# HSDL-9100.net
KiCad netlist of a schematic drawn in EAGLE
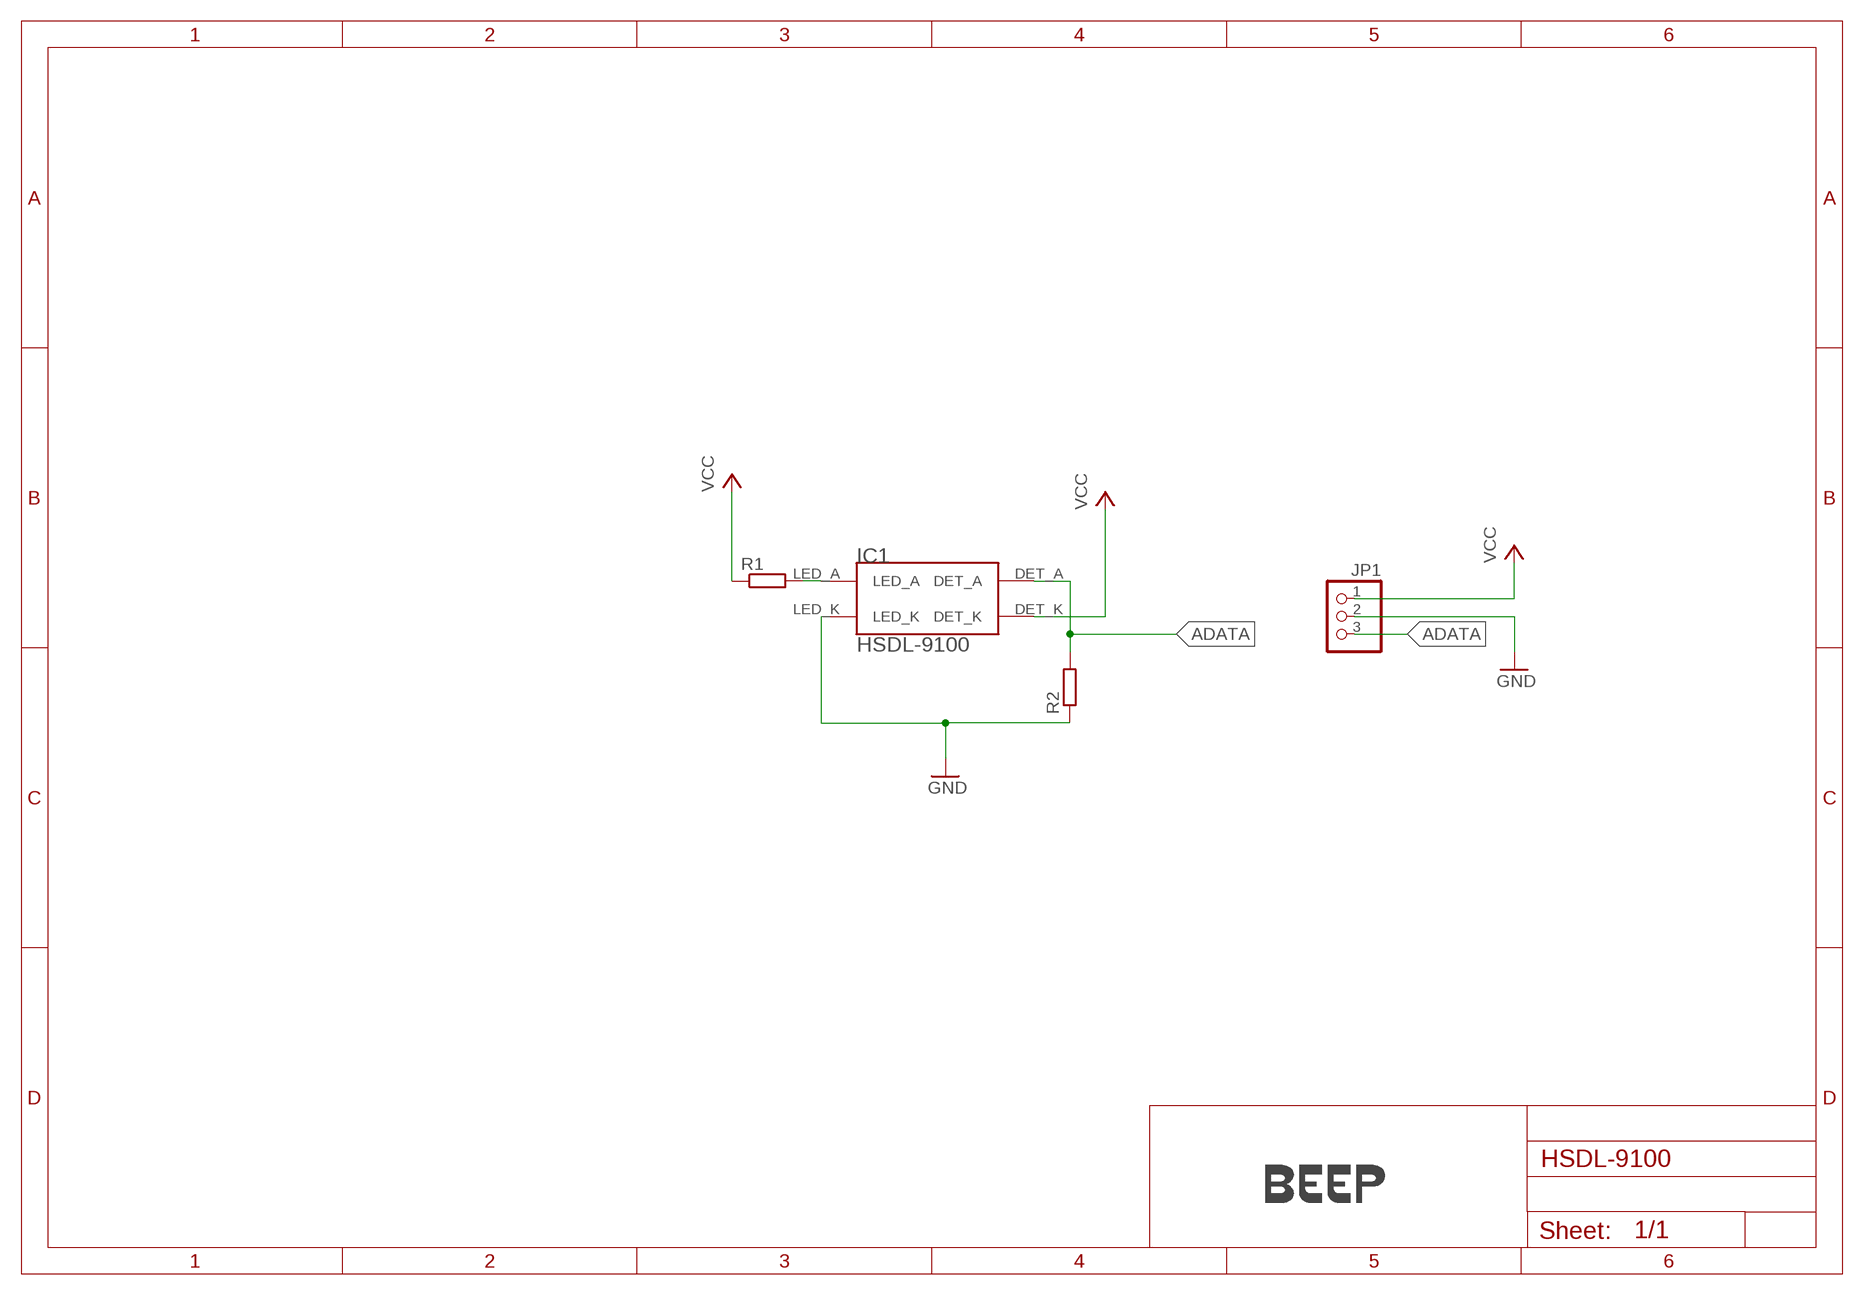
[diagram p0: schematic, sheet 1]

(export (version "E")
  (design (tool "Eeschema 10.0.6"))
  (components
    (comp (ref "IC1")
      (value "HSDL-9100")
      (footprint "eagle-import:HSDL-9100")
      (libsource (lib "eagle-import") (part "HSDL-9100"))
    )
    (comp (ref "JP1")
      (value "PINHD-1X3")
      (footprint "eagle-import:1X03")
      (libsource (lib "eagle-import") (part "PINHD-1X3"))
    )
    (comp (ref "R1")
      (value "R-EU_M0805")
      (footprint "eagle-import:M0805")
      (libsource (lib "eagle-import") (part "R-EU_M0805"))
    )
    (comp (ref "R2")
      (value "R-EU_M0805")
      (footprint "eagle-import:M0805")
      (libsource (lib "eagle-import") (part "R-EU_M0805"))
    )
    (comp (ref "U$1")
      (value "LOGO-COPPER3")
      (footprint "eagle-import:COPPER3")
      (libsource (lib "eagle-import") (part "LOGO-COPPER3"))
    )
  )
  (nets
    (net (code "1") (name "ADATA") (class "Default")
      (node (ref "IC1") (pin "DET_A") (pinfunction "DET_A_DET_A") (pintype "bidirectional"))
      (node (ref "JP1") (pin "3") (pinfunction "3_3") (pintype "passive"))
      (node (ref "R2") (pin "2") (pinfunction "2_2") (pintype "passive"))
    )
    (net (code "2") (name "GND") (class "Default")
      (node (ref "IC1") (pin "LED_K") (pinfunction "LED_K_LED_K") (pintype "bidirectional"))
      (node (ref "JP1") (pin "2") (pinfunction "2_2") (pintype "passive"))
      (node (ref "R2") (pin "1") (pinfunction "1_1") (pintype "passive"))
    )
    (net (code "3") (name "Net-(IC1-PadLED_A)") (class "Default")
      (node (ref "IC1") (pin "LED_A") (pinfunction "LED_A_LED_A") (pintype "bidirectional"))
      (node (ref "R1") (pin "2") (pinfunction "2_2") (pintype "passive"))
    )
    (net (code "4") (name "VCC") (class "Default")
      (node (ref "IC1") (pin "DET_K") (pinfunction "DET_K_DET_K") (pintype "bidirectional"))
      (node (ref "JP1") (pin "1") (pinfunction "1_1") (pintype "passive"))
      (node (ref "R1") (pin "1") (pinfunction "1_1") (pintype "passive"))
    )
  )
)
